# 6502v2_lcd_connector.net
KiCad netlist of a schematic drawn in EasyEDA
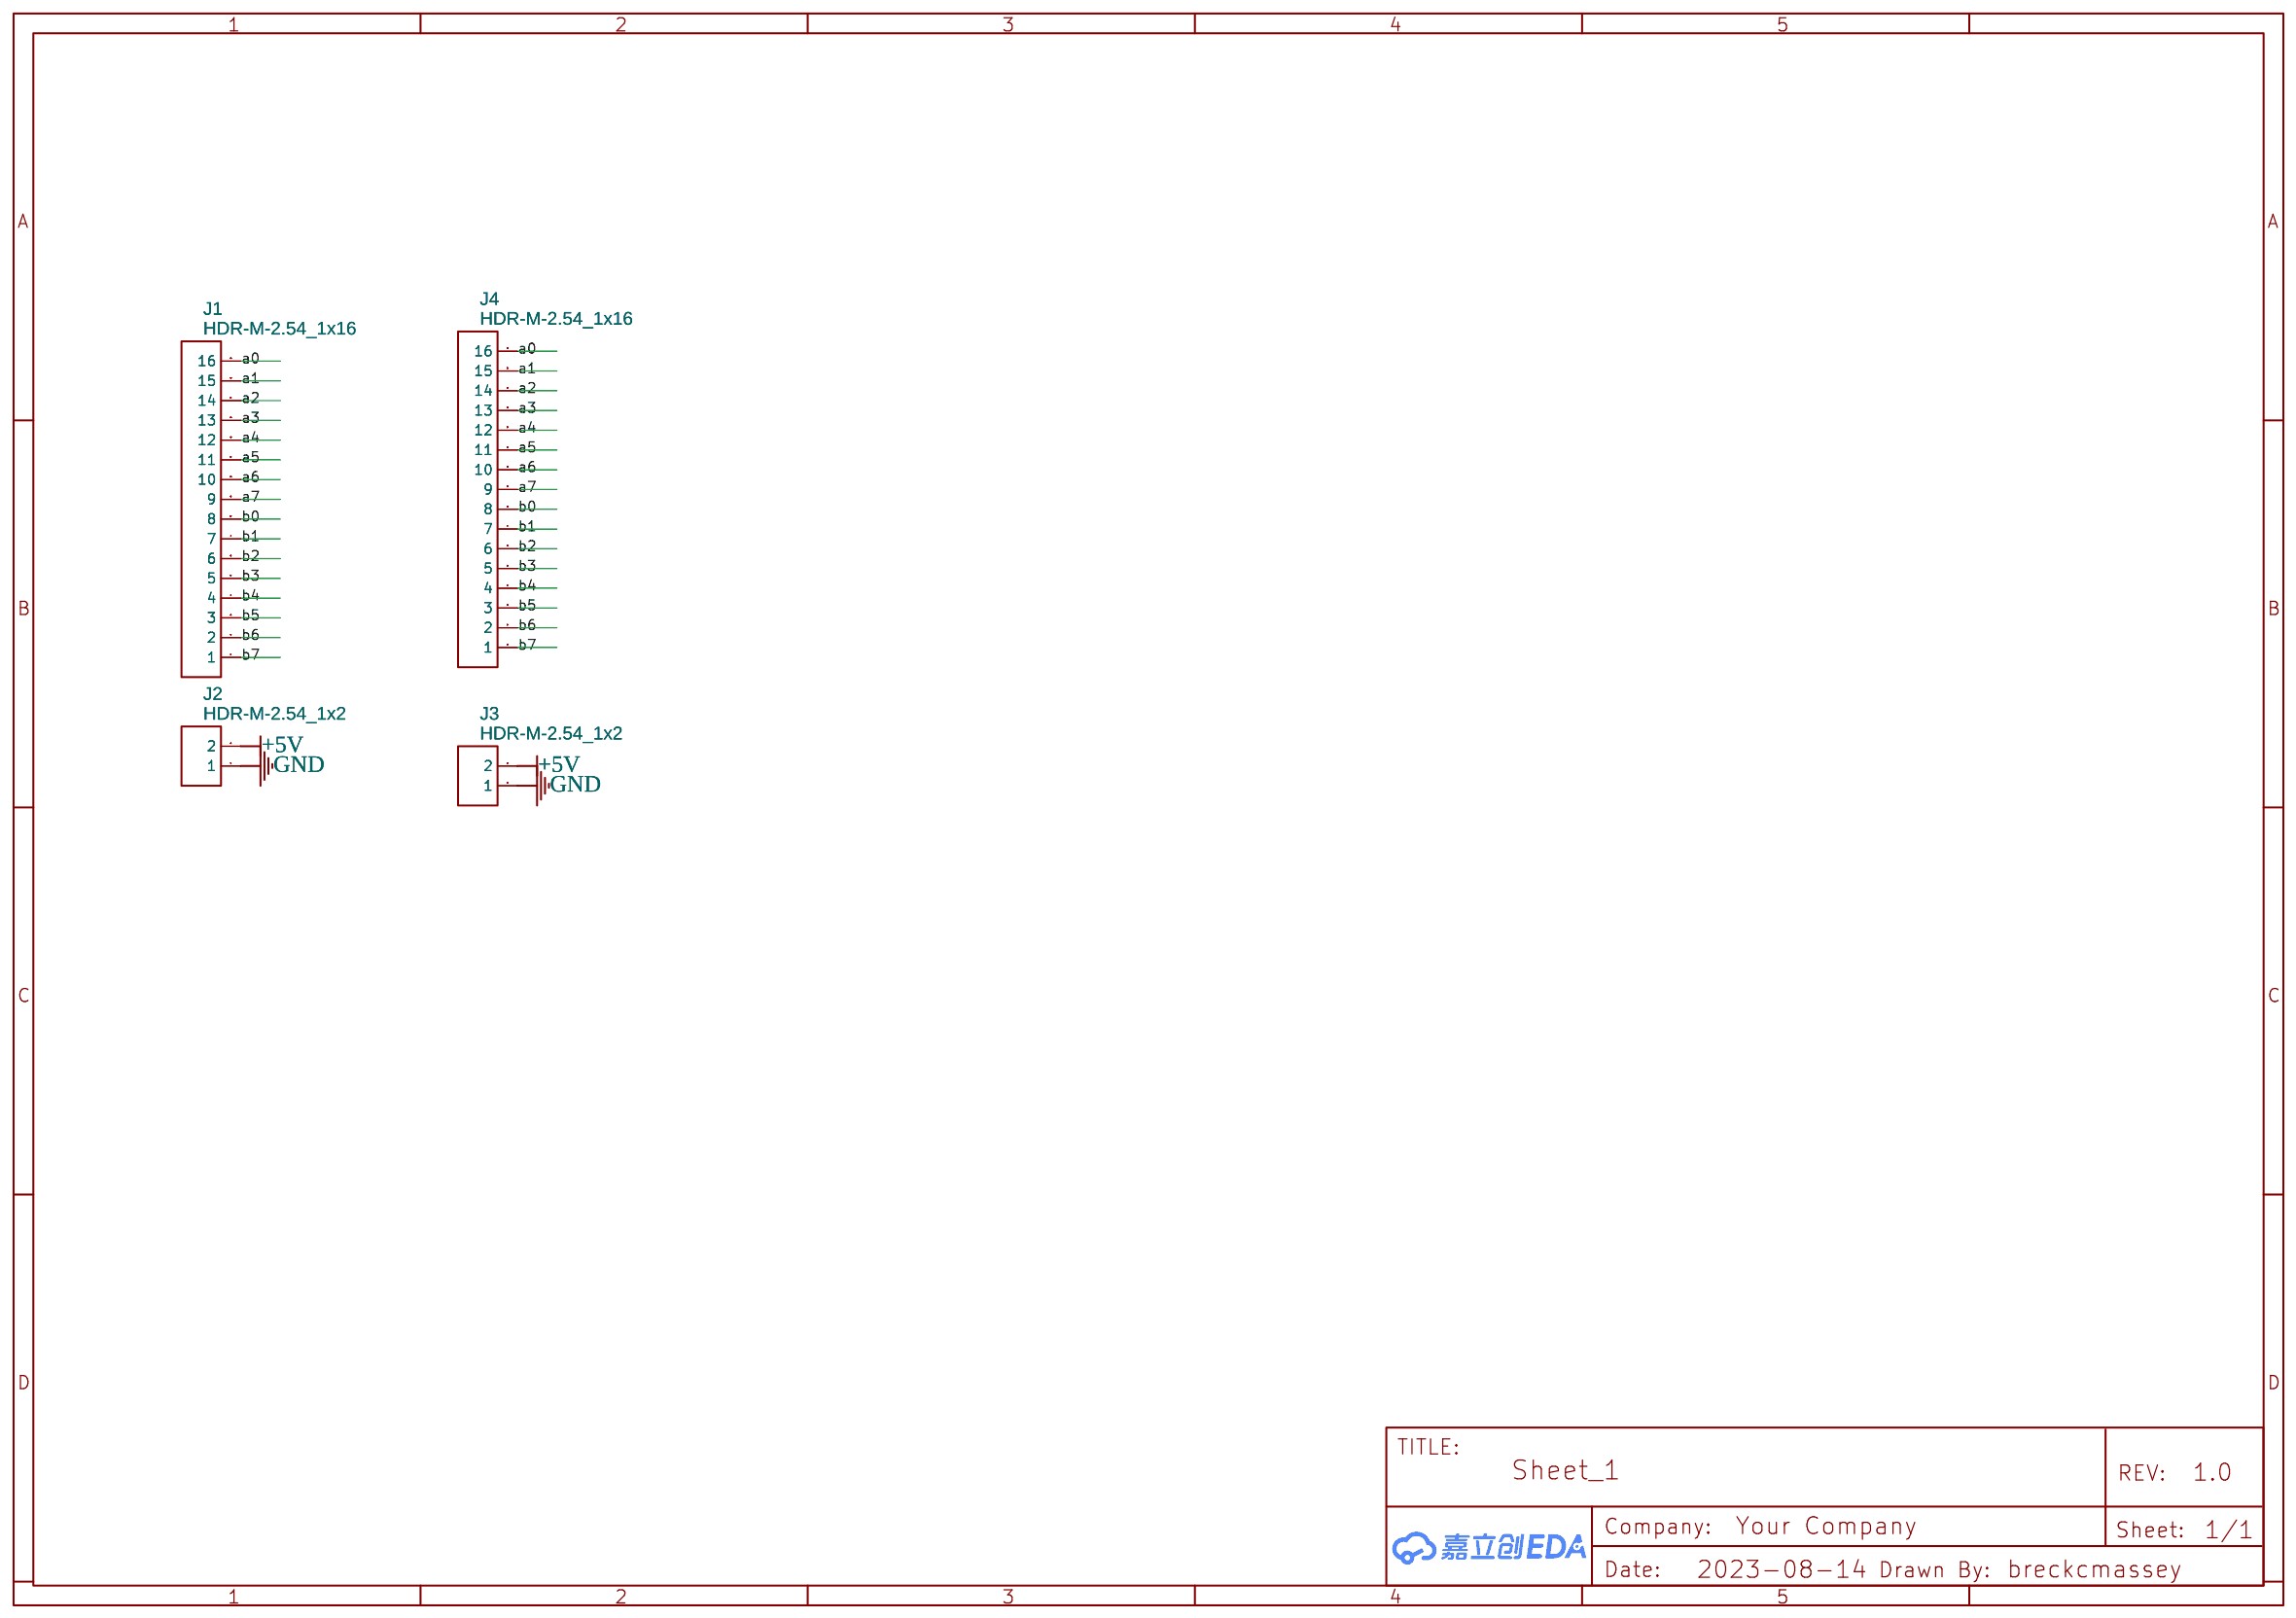
[diagram p0: schematic sheet]

(export (version "E")
  (design (tool "Eeschema 10.0.6"))
  (components
    (comp (ref "J1") (value "HDR-M-2.54_1x16") (libsource (lib "") (part "HDR-M-2.54_1x16")))
    (comp (ref "J2")
      (value "HDR-M-2.54_1x2")
      (fields (field (name "BOM_Supplier Part") "C124375"))
      (libsource (lib "") (part "HDR-M-2.54_1x2"))
    )
    (comp (ref "J3")
      (value "HDR-M-2.54_1x2")
      (fields (field (name "BOM_Supplier Part") "C124375"))
      (libsource (lib "") (part "HDR-M-2.54_1x2"))
    )
    (comp (ref "J4") (value "HDR-M-2.54_1x16") (libsource (lib "") (part "HDR-M-2.54_1x16")))
  )
  (nets
    (net (code "1") (name "+5V") (class "Default")
      (node (ref "J2") (pin "2") (pinfunction "2_2") (pintype "unspecified"))
      (node (ref "J3") (pin "2") (pinfunction "2_2") (pintype "unspecified"))
    )
    (net (code "2") (name "/a0") (class "Default")
      (node (ref "J1") (pin "16") (pinfunction "16_16") (pintype "unspecified"))
      (node (ref "J4") (pin "16") (pinfunction "16_16") (pintype "unspecified"))
    )
    (net (code "3") (name "/a1") (class "Default")
      (node (ref "J1") (pin "15") (pinfunction "15_15") (pintype "unspecified"))
      (node (ref "J4") (pin "15") (pinfunction "15_15") (pintype "unspecified"))
    )
    (net (code "4") (name "/a2") (class "Default")
      (node (ref "J1") (pin "14") (pinfunction "14_14") (pintype "unspecified"))
      (node (ref "J4") (pin "14") (pinfunction "14_14") (pintype "unspecified"))
    )
    (net (code "5") (name "/a3") (class "Default")
      (node (ref "J1") (pin "13") (pinfunction "13_13") (pintype "unspecified"))
      (node (ref "J4") (pin "13") (pinfunction "13_13") (pintype "unspecified"))
    )
    (net (code "6") (name "/a4") (class "Default")
      (node (ref "J1") (pin "12") (pinfunction "12_12") (pintype "unspecified"))
      (node (ref "J4") (pin "12") (pinfunction "12_12") (pintype "unspecified"))
    )
    (net (code "7") (name "/a5") (class "Default")
      (node (ref "J1") (pin "11") (pinfunction "11_11") (pintype "unspecified"))
      (node (ref "J4") (pin "11") (pinfunction "11_11") (pintype "unspecified"))
    )
    (net (code "8") (name "/a6") (class "Default")
      (node (ref "J1") (pin "10") (pinfunction "10_10") (pintype "unspecified"))
      (node (ref "J4") (pin "10") (pinfunction "10_10") (pintype "unspecified"))
    )
    (net (code "9") (name "/a7") (class "Default")
      (node (ref "J1") (pin "9") (pinfunction "9_9") (pintype "unspecified"))
      (node (ref "J4") (pin "9") (pinfunction "9_9") (pintype "unspecified"))
    )
    (net (code "10") (name "/b0") (class "Default")
      (node (ref "J1") (pin "8") (pinfunction "8_8") (pintype "unspecified"))
      (node (ref "J4") (pin "8") (pinfunction "8_8") (pintype "unspecified"))
    )
    (net (code "11") (name "/b1") (class "Default")
      (node (ref "J1") (pin "7") (pinfunction "7_7") (pintype "unspecified"))
      (node (ref "J4") (pin "7") (pinfunction "7_7") (pintype "unspecified"))
    )
    (net (code "12") (name "/b2") (class "Default")
      (node (ref "J1") (pin "6") (pinfunction "6_6") (pintype "unspecified"))
      (node (ref "J4") (pin "6") (pinfunction "6_6") (pintype "unspecified"))
    )
    (net (code "13") (name "/b3") (class "Default")
      (node (ref "J1") (pin "5") (pinfunction "5_5") (pintype "unspecified"))
      (node (ref "J4") (pin "5") (pinfunction "5_5") (pintype "unspecified"))
    )
    (net (code "14") (name "/b4") (class "Default")
      (node (ref "J1") (pin "4") (pinfunction "4_4") (pintype "unspecified"))
      (node (ref "J4") (pin "4") (pinfunction "4_4") (pintype "unspecified"))
    )
    (net (code "15") (name "/b5") (class "Default")
      (node (ref "J1") (pin "3") (pinfunction "3_3") (pintype "unspecified"))
      (node (ref "J4") (pin "3") (pinfunction "3_3") (pintype "unspecified"))
    )
    (net (code "16") (name "/b6") (class "Default")
      (node (ref "J1") (pin "2") (pinfunction "2_2") (pintype "unspecified"))
      (node (ref "J4") (pin "2") (pinfunction "2_2") (pintype "unspecified"))
    )
    (net (code "17") (name "/b7") (class "Default")
      (node (ref "J1") (pin "1") (pinfunction "1_1") (pintype "unspecified"))
      (node (ref "J4") (pin "1") (pinfunction "1_1") (pintype "unspecified"))
    )
    (net (code "18") (name "GND") (class "Default")
      (node (ref "J2") (pin "1") (pinfunction "1_1") (pintype "unspecified"))
      (node (ref "J3") (pin "1") (pinfunction "1_1") (pintype "unspecified"))
    )
  )
)
